# MCU.net
KiCad netlist of a schematic drawn in Altium Designer
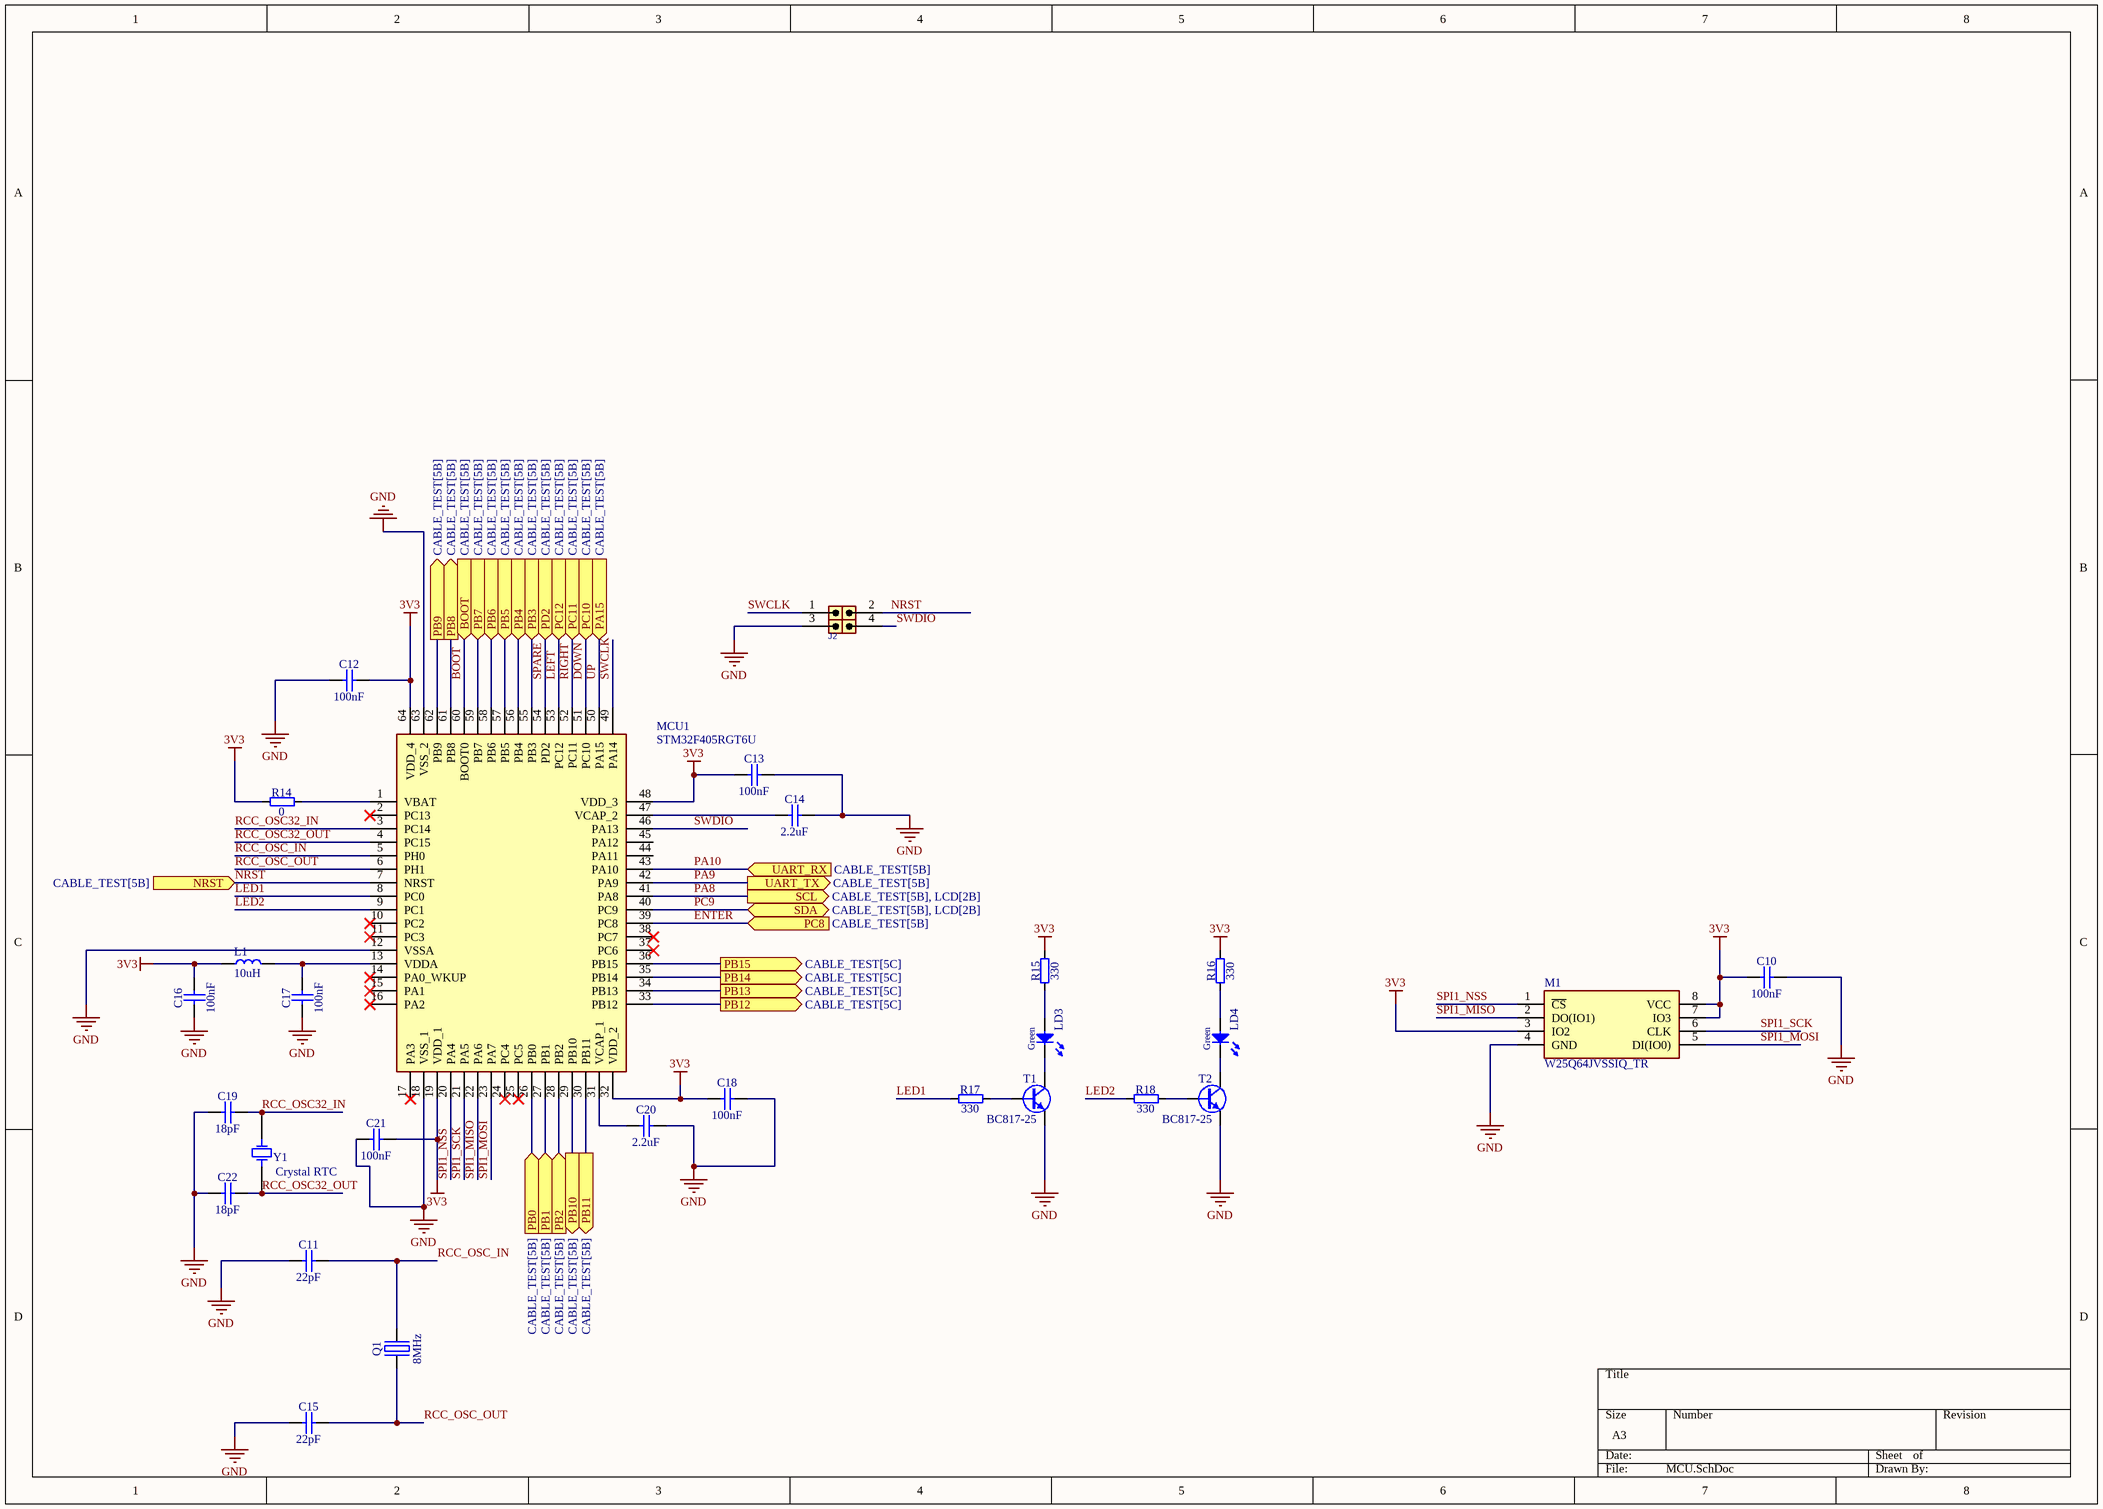
[diagram p0: MCU.SchDoc]

(export (version "E")
  (design (tool "Eeschema 10.0.6"))
  (components
    (comp (ref "C10")
      (value "100nF")
      (footprint "CAPC2012X135N")
      (description "Non-polarised capacitor")
      (fields
        (field (name "PART NUMBER") "CC0805_1.2PF_50V_0.25PF_NP0")
        (field (name "VOLTAGE") "50V")
        (field (name "AUTHOR") "CERN DEM JLC")
      )
      (libsource (lib "Capacitors") (part "Capacitor - non polarized"))
    )
    (comp (ref "C11")
      (value "22pF")
      (footprint "CAPC2012X135N")
      (description "Non-polarised capacitor")
      (fields
        (field (name "PART NUMBER") "CC0805_100NF_50V_10%_X7R")
        (field (name "VOLTAGE") "50V")
        (field (name "AUTHOR") "CERN DEM JLC")
      )
      (libsource (lib "Capacitors") (part "Capacitor - non polarized"))
    )
    (comp (ref "C12")
      (value "100nF")
      (footprint "CAPC2012X135N")
      (description "Non-polarised capacitor")
      (fields
        (field (name "PART NUMBER") "CC0805_100NF_50V_10%_X7R")
        (field (name "VOLTAGE") "50V")
        (field (name "AUTHOR") "CERN DEM JLC")
      )
      (libsource (lib "Capacitors") (part "Capacitor - non polarized"))
    )
    (comp (ref "C13")
      (value "100nF")
      (footprint "CAPC2012X135N")
      (description "Non-polarised capacitor")
      (fields
        (field (name "PART NUMBER") "CC0805_100NF_50V_10%_X7R")
        (field (name "VOLTAGE") "50V")
        (field (name "AUTHOR") "CERN DEM JLC")
      )
      (libsource (lib "Capacitors") (part "Capacitor - non polarized"))
    )
    (comp (ref "C14")
      (value "2.2uF")
      (footprint "CAPC2012X135N")
      (description "Non-polarised capacitor")
      (fields
        (field (name "PART NUMBER") "CC0805_100NF_50V_10%_X7R")
        (field (name "VOLTAGE") "50V")
        (field (name "AUTHOR") "CERN DEM JLC")
      )
      (libsource (lib "Capacitors") (part "Capacitor - non polarized"))
    )
    (comp (ref "C15")
      (value "22pF")
      (footprint "CAPC2012X135N")
      (description "Non-polarised capacitor")
      (fields
        (field (name "PART NUMBER") "CC0805_100NF_50V_10%_X7R")
        (field (name "VOLTAGE") "50V")
        (field (name "AUTHOR") "CERN DEM JLC")
      )
      (libsource (lib "Capacitors") (part "Capacitor - non polarized"))
    )
    (comp (ref "C16")
      (value "100nF")
      (footprint "CAPC2012X135N")
      (description "Non-polarised capacitor")
      (fields
        (field (name "PART NUMBER") "CC0805_100NF_50V_10%_X7R")
        (field (name "VOLTAGE") "50V")
        (field (name "AUTHOR") "CERN DEM JLC")
      )
      (libsource (lib "Capacitors") (part "Capacitor - non polarized"))
    )
    (comp (ref "C17")
      (value "100nF")
      (footprint "CAPC2012X135N")
      (description "Non-polarised capacitor")
      (fields
        (field (name "PART NUMBER") "CC0805_100NF_50V_10%_X7R")
        (field (name "VOLTAGE") "50V")
        (field (name "AUTHOR") "CERN DEM JLC")
      )
      (libsource (lib "Capacitors") (part "Capacitor - non polarized"))
    )
    (comp (ref "C18")
      (value "100nF")
      (footprint "CAPC2012X135N")
      (description "Non-polarised capacitor")
      (fields
        (field (name "PART NUMBER") "CC0805_100NF_50V_10%_X7R")
        (field (name "VOLTAGE") "50V")
        (field (name "AUTHOR") "CERN DEM JLC")
      )
      (libsource (lib "Capacitors") (part "Capacitor - non polarized"))
    )
    (comp (ref "C19")
      (value "18pF")
      (footprint "CAPC2012X135N")
      (description "Non-polarised capacitor")
      (fields
        (field (name "PART NUMBER") "CC0805_100NF_50V_10%_X7R")
        (field (name "VOLTAGE") "50V")
        (field (name "AUTHOR") "CERN DEM JLC")
      )
      (libsource (lib "Capacitors") (part "Capacitor - non polarized"))
    )
    (comp (ref "C20")
      (value "2.2uF")
      (footprint "CAPC2012X135N")
      (description "Non-polarised capacitor")
      (fields
        (field (name "PART NUMBER") "CC0805_100NF_50V_10%_X7R")
        (field (name "VOLTAGE") "50V")
        (field (name "AUTHOR") "CERN DEM JLC")
      )
      (libsource (lib "Capacitors") (part "Capacitor - non polarized"))
    )
    (comp (ref "C21")
      (value "100nF")
      (footprint "CAPC2012X135N")
      (description "Non-polarised capacitor")
      (fields
        (field (name "PART NUMBER") "CC0805_100NF_50V_10%_X7R")
        (field (name "VOLTAGE") "50V")
        (field (name "AUTHOR") "CERN DEM JLC")
      )
      (libsource (lib "Capacitors") (part "Capacitor - non polarized"))
    )
    (comp (ref "C22")
      (value "18pF")
      (footprint "CAPC2012X135N")
      (description "Non-polarised capacitor")
      (fields
        (field (name "PART NUMBER") "CC0805_100NF_50V_10%_X7R")
        (field (name "VOLTAGE") "50V")
        (field (name "AUTHOR") "CERN DEM JLC")
      )
      (libsource (lib "Capacitors") (part "Capacitor - non polarized"))
    )
    (comp (ref "J2")
      (value "Female Header dual 2")
      (footprint "HDR_F_2X2")
      (description "Female, pitch: 2.54mm")
      (libsource (lib "DSC-T.RControlBoard") (part "Female Header dual 2"))
    )
    (comp (ref "L1")
      (value "10uH")
      (footprint "L0805")
      (description "Inductor SMD NC 0805")
      (libsource (lib "DSC-T.RControlBoard") (part "Inductor SMD NC 0805"))
    )
    (comp (ref "LD3")
      (value "Green")
      (footprint "LED_3MM_GREEN_1C-2A")
      (description "LED Green 1C 2A")
      (fields
        (field (name "PART NUMBER") "LED_AVAGO_HLMP-1790")
        (field (name "MANUFACTURER") "AVAGO TECHNOLOGIES")
        (field (name "AUTHOR") "CERN DEM JLC")
      )
      (libsource (lib "ICs And Semiconductors") (part "LED Green 1C 2A"))
    )
    (comp (ref "LD4")
      (value "Green")
      (footprint "LED_3MM_GREEN_1C-2A")
      (description "LED Green 1C 2A")
      (fields
        (field (name "PART NUMBER") "LED_AVAGO_HLMP-1790")
        (field (name "MANUFACTURER") "AVAGO TECHNOLOGIES")
        (field (name "AUTHOR") "CERN DEM JLC")
      )
      (libsource (lib "ICs And Semiconductors") (part "LED Green 1C 2A"))
    )
    (comp (ref "M1")
      (value "W25Q64JVSSIQ_TR")
      (footprint "LORA:SOIC127P790X216-8N")
      (description "Integrated Circuit")
      (fields
        (field (name "MANUFACTURER_PART_NUMBER") "W25Q64JVSSIQ TR")
        (field (name "MOUSER PART NUMBER") "454-W25Q64JVSSIQTR")
      )
      (libsource (lib "*") (part "W25Q64JVSSIQ_TR"))
    )
    (comp (ref "MCU1")
      (value "STM32F405RGT6U")
      (footprint "LORA:QFP50P1200X1200X160-64N")
      (description "Integrated Circuit")
      (fields (field (name "MOUSER PART NUMBER") "511-STM32F405RGT6U"))
      (libsource (lib "*") (part "STM32F405RGT6U"))
    )
    (comp (ref "Q1")
      (value "8MHz")
      (footprint "XTAL_CTS_ATS")
      (description "Quartz Crystal")
      (fields
        (field (name "PART NUMBER") "XTAL_10MHZ_CTS_ATS100B-E")
        (field (name "MANUFACTURER") "CTS")
        (field (name "AUTHOR") "CERN DEM HF")
      )
      (libsource (lib "ICs And Semiconductors") (part "Quartz Crystal"))
    )
    (comp (ref "R14")
      (value "0")
      (footprint "RESC2012X60N")
      (description "Resistor - 1%")
      (fields
        (field (name "PART NUMBER") "R0805_24K_1%_0.125W_100PPM")
        (field (name "POWER") "0.125W")
        (field (name "AUTHOR") "CERN DEM JLC")
      )
      (libsource (lib "Resistors") (part "Resistor - 1%"))
    )
    (comp (ref "R15")
      (value "330")
      (footprint "RESC2012X60N")
      (description "Resistor - 1%")
      (fields
        (field (name "PART NUMBER") "R0805_24K_1%_0.125W_100PPM")
        (field (name "POWER") "0.125W")
        (field (name "AUTHOR") "CERN DEM JLC")
      )
      (libsource (lib "Resistors") (part "Resistor - 1%"))
    )
    (comp (ref "R16")
      (value "330")
      (footprint "RESC2012X60N")
      (description "Resistor - 1%")
      (fields
        (field (name "PART NUMBER") "R0805_24K_1%_0.125W_100PPM")
        (field (name "POWER") "0.125W")
        (field (name "AUTHOR") "CERN DEM JLC")
      )
      (libsource (lib "Resistors") (part "Resistor - 1%"))
    )
    (comp (ref "R17")
      (value "330")
      (footprint "RESC2012X60N")
      (description "Resistor - 1%")
      (fields
        (field (name "PART NUMBER") "R0805_24K_1%_0.125W_100PPM")
        (field (name "POWER") "0.125W")
        (field (name "AUTHOR") "CERN DEM JLC")
      )
      (libsource (lib "Resistors") (part "Resistor - 1%"))
    )
    (comp (ref "R18")
      (value "330")
      (footprint "RESC2012X60N")
      (description "Resistor - 1%")
      (fields
        (field (name "PART NUMBER") "R0805_24K_1%_0.125W_100PPM")
        (field (name "POWER") "0.125W")
        (field (name "AUTHOR") "CERN DEM JLC")
      )
      (libsource (lib "Resistors") (part "Resistor - 1%"))
    )
    (comp (ref "T1")
      (value "BC817-25")
      (footprint "SOT95P230X110-3N")
      (description "NPN Transistor")
      (fields (field (name "MANUFACTURER") "NXP SEMICONDUCTORS") (field (name "AUTHOR") "CERN DEM JLC"))
      (libsource (lib "ICs And Semiconductors") (part "NPN B1 E2 C3"))
    )
    (comp (ref "T2")
      (value "BC817-25")
      (footprint "SOT95P230X110-3N")
      (description "NPN Transistor")
      (fields (field (name "MANUFACTURER") "NXP SEMICONDUCTORS") (field (name "AUTHOR") "CERN DEM JLC"))
      (libsource (lib "ICs And Semiconductors") (part "NPN B1 E2 C3"))
    )
    (comp (ref "Y1")
      (value "Crystal RTC")
      (footprint "Crystal Clock")
      (description "Crystal")
      (libsource (lib "DSC-T.RControlBoard") (part "Crystal RTC"))
    )
  )
  (nets
    (net (code "1") (name "/BOOT") (class "Default")
      (node (ref "MCU1") (pin "60") (pinfunction "BOOT0_60") (pintype "passive"))
    )
    (net (code "2") (name "/DOWN") (class "Default")
      (node (ref "MCU1") (pin "51") (pinfunction "PC10_51") (pintype "passive"))
    )
    (net (code "3") (name "/ENTER") (class "Default")
      (node (ref "MCU1") (pin "39") (pinfunction "PC8_39") (pintype "passive"))
    )
    (net (code "4") (name "/LED1") (class "Default")
      (node (ref "MCU1") (pin "8") (pinfunction "PC0_8") (pintype "passive"))
      (node (ref "R17") (pin "1") (pinfunction "1_1") (pintype "passive"))
    )
    (net (code "5") (name "/LED2") (class "Default")
      (node (ref "MCU1") (pin "9") (pinfunction "PC1_9") (pintype "passive"))
      (node (ref "R18") (pin "1") (pinfunction "1_1") (pintype "passive"))
    )
    (net (code "6") (name "/LEFT") (class "Default")
      (node (ref "MCU1") (pin "53") (pinfunction "PC12_53") (pintype "passive"))
    )
    (net (code "7") (name "/NRST") (class "Default")
      (node (ref "J2") (pin "2") (pinfunction "2_2") (pintype "passive"))
      (node (ref "MCU1") (pin "7") (pinfunction "NRST_7") (pintype "passive"))
    )
    (net (code "8") (name "/PA8") (class "Default")
      (node (ref "MCU1") (pin "41") (pinfunction "PA8_41") (pintype "passive"))
    )
    (net (code "9") (name "/PA9") (class "Default")
      (node (ref "MCU1") (pin "42") (pinfunction "PA9_42") (pintype "passive"))
    )
    (net (code "10") (name "/PA10") (class "Default")
      (node (ref "MCU1") (pin "43") (pinfunction "PA10_43") (pintype "passive"))
    )
    (net (code "11") (name "/PB0") (class "Default")
      (node (ref "MCU1") (pin "26") (pinfunction "PB0_26") (pintype "passive"))
    )
    (net (code "12") (name "/PB1") (class "Default")
      (node (ref "MCU1") (pin "27") (pinfunction "PB1_27") (pintype "passive"))
    )
    (net (code "13") (name "/PB2") (class "Default")
      (node (ref "MCU1") (pin "28") (pinfunction "PB2_28") (pintype "passive"))
    )
    (net (code "14") (name "/PB3") (class "Default")
      (node (ref "MCU1") (pin "55") (pinfunction "PB3_55") (pintype "passive"))
    )
    (net (code "15") (name "/PB4") (class "Default")
      (node (ref "MCU1") (pin "56") (pinfunction "PB4_56") (pintype "passive"))
    )
    (net (code "16") (name "/PB5") (class "Default")
      (node (ref "MCU1") (pin "57") (pinfunction "PB5_57") (pintype "passive"))
    )
    (net (code "17") (name "/PB6") (class "Default")
      (node (ref "MCU1") (pin "58") (pinfunction "PB6_58") (pintype "passive"))
    )
    (net (code "18") (name "/PB7") (class "Default")
      (node (ref "MCU1") (pin "59") (pinfunction "PB7_59") (pintype "passive"))
    )
    (net (code "19") (name "/PB8") (class "Default")
      (node (ref "MCU1") (pin "61") (pinfunction "PB8_61") (pintype "passive"))
    )
    (net (code "20") (name "/PB9") (class "Default")
      (node (ref "MCU1") (pin "62") (pinfunction "PB9_62") (pintype "passive"))
    )
    (net (code "21") (name "/PB10") (class "Default")
      (node (ref "MCU1") (pin "29") (pinfunction "PB10_29") (pintype "passive"))
    )
    (net (code "22") (name "/PB11") (class "Default")
      (node (ref "MCU1") (pin "30") (pinfunction "PB11_30") (pintype "passive"))
    )
    (net (code "23") (name "/PB12") (class "Default")
      (node (ref "MCU1") (pin "33") (pinfunction "PB12_33") (pintype "passive"))
    )
    (net (code "24") (name "/PB13") (class "Default")
      (node (ref "MCU1") (pin "34") (pinfunction "PB13_34") (pintype "passive"))
    )
    (net (code "25") (name "/PB14") (class "Default")
      (node (ref "MCU1") (pin "35") (pinfunction "PB14_35") (pintype "passive"))
    )
    (net (code "26") (name "/PB15") (class "Default")
      (node (ref "MCU1") (pin "36") (pinfunction "PB15_36") (pintype "passive"))
    )
    (net (code "27") (name "/PC9") (class "Default")
      (node (ref "MCU1") (pin "40") (pinfunction "PC9_40") (pintype "passive"))
    )
    (net (code "28") (name "/RCC_OSC32_IN") (class "Default")
      (node (ref "C19") (pin "2") (pinfunction "2_2") (pintype "passive"))
      (node (ref "MCU1") (pin "3") (pinfunction "PC14_3") (pintype "passive"))
      (node (ref "Y1") (pin "1") (pinfunction "1_1") (pintype "passive"))
    )
    (net (code "29") (name "/RCC_OSC32_OUT") (class "Default")
      (node (ref "C22") (pin "2") (pinfunction "2_2") (pintype "passive"))
      (node (ref "MCU1") (pin "4") (pinfunction "PC15_4") (pintype "passive"))
      (node (ref "Y1") (pin "2") (pinfunction "2_2") (pintype "passive"))
    )
    (net (code "30") (name "/RCC_OSC_IN") (class "Default")
      (node (ref "C11") (pin "2") (pinfunction "2_2") (pintype "passive"))
      (node (ref "MCU1") (pin "5") (pinfunction "PH0_5") (pintype "passive"))
      (node (ref "Q1") (pin "2") (pinfunction "OSC2_2") (pintype "passive"))
    )
    (net (code "31") (name "/RCC_OSC_OUT") (class "Default")
      (node (ref "C15") (pin "2") (pinfunction "2_2") (pintype "passive"))
      (node (ref "MCU1") (pin "6") (pinfunction "PH1_6") (pintype "passive"))
      (node (ref "Q1") (pin "1") (pinfunction "OSC1_1") (pintype "passive"))
    )
    (net (code "32") (name "/RIGHT") (class "Default")
      (node (ref "MCU1") (pin "52") (pinfunction "PC11_52") (pintype "passive"))
    )
    (net (code "33") (name "/SPARE") (class "Default")
      (node (ref "MCU1") (pin "54") (pinfunction "PD2_54") (pintype "passive"))
    )
    (net (code "34") (name "/SPI1_MISO") (class "Default")
      (node (ref "M1") (pin "2") (pinfunction "DO(IO1)_2") (pintype "passive"))
      (node (ref "MCU1") (pin "22") (pinfunction "PA6_22") (pintype "passive"))
    )
    (net (code "35") (name "/SPI1_MOSI") (class "Default")
      (node (ref "M1") (pin "5") (pinfunction "DI(IO0)_5") (pintype "passive"))
      (node (ref "MCU1") (pin "23") (pinfunction "PA7_23") (pintype "passive"))
    )
    (net (code "36") (name "/SPI1_NSS") (class "Default")
      (node (ref "M1") (pin "1") (pinfunction "~{CS}_1") (pintype "passive"))
      (node (ref "MCU1") (pin "20") (pinfunction "PA4_20") (pintype "passive"))
    )
    (net (code "37") (name "/SPI1_SCK") (class "Default")
      (node (ref "M1") (pin "6") (pinfunction "CLK_6") (pintype "passive"))
      (node (ref "MCU1") (pin "21") (pinfunction "PA5_21") (pintype "passive"))
    )
    (net (code "38") (name "/SWCLK") (class "Default")
      (node (ref "J2") (pin "1") (pinfunction "1_1") (pintype "passive"))
      (node (ref "MCU1") (pin "49") (pinfunction "PA14_49") (pintype "passive"))
    )
    (net (code "39") (name "/SWDIO") (class "Default")
      (node (ref "J2") (pin "4") (pinfunction "4_4") (pintype "passive"))
      (node (ref "MCU1") (pin "46") (pinfunction "PA13_46") (pintype "passive"))
    )
    (net (code "40") (name "/UP") (class "Default")
      (node (ref "MCU1") (pin "50") (pinfunction "PA15_50") (pintype "passive"))
    )
    (net (code "41") (name "3V3") (class "Default")
      (node (ref "C10") (pin "1") (pinfunction "1_1") (pintype "passive"))
      (node (ref "C12") (pin "2") (pinfunction "2_2") (pintype "passive"))
      (node (ref "C13") (pin "1") (pinfunction "1_1") (pintype "passive"))
      (node (ref "C16") (pin "2") (pinfunction "2_2") (pintype "passive"))
      (node (ref "C18") (pin "1") (pinfunction "1_1") (pintype "passive"))
      (node (ref "C21") (pin "2") (pinfunction "2_2") (pintype "passive"))
      (node (ref "L1") (pin "1") (pinfunction "1_1") (pintype "passive"))
      (node (ref "M1") (pin "3") (pinfunction "IO2_3") (pintype "passive"))
      (node (ref "M1") (pin "7") (pinfunction "IO3_7") (pintype "passive"))
      (node (ref "M1") (pin "8") (pinfunction "VCC_8") (pintype "passive"))
      (node (ref "MCU1") (pin "19") (pinfunction "VDD_1_19") (pintype "passive"))
      (node (ref "MCU1") (pin "32") (pinfunction "VDD_2_32") (pintype "passive"))
      (node (ref "MCU1") (pin "48") (pinfunction "VDD_3_48") (pintype "passive"))
      (node (ref "MCU1") (pin "64") (pinfunction "VDD_4_64") (pintype "passive"))
      (node (ref "R14") (pin "1") (pinfunction "1_1") (pintype "passive"))
      (node (ref "R15") (pin "2") (pinfunction "2_2") (pintype "passive"))
      (node (ref "R16") (pin "2") (pinfunction "2_2") (pintype "passive"))
    )
    (net (code "42") (name "GND") (class "Default")
      (node (ref "C10") (pin "2") (pinfunction "2_2") (pintype "passive"))
      (node (ref "C11") (pin "1") (pinfunction "1_1") (pintype "passive"))
      (node (ref "C12") (pin "1") (pinfunction "1_1") (pintype "passive"))
      (node (ref "C13") (pin "2") (pinfunction "2_2") (pintype "passive"))
      (node (ref "C14") (pin "2") (pinfunction "2_2") (pintype "passive"))
      (node (ref "C15") (pin "1") (pinfunction "1_1") (pintype "passive"))
      (node (ref "C16") (pin "1") (pinfunction "1_1") (pintype "passive"))
      (node (ref "C17") (pin "1") (pinfunction "1_1") (pintype "passive"))
      (node (ref "C18") (pin "2") (pinfunction "2_2") (pintype "passive"))
      (node (ref "C19") (pin "1") (pinfunction "1_1") (pintype "passive"))
      (node (ref "C20") (pin "2") (pinfunction "2_2") (pintype "passive"))
      (node (ref "C21") (pin "1") (pinfunction "1_1") (pintype "passive"))
      (node (ref "C22") (pin "1") (pinfunction "1_1") (pintype "passive"))
      (node (ref "J2") (pin "3") (pinfunction "3_3") (pintype "passive"))
      (node (ref "M1") (pin "4") (pinfunction "GND_4") (pintype "passive"))
      (node (ref "MCU1") (pin "12") (pinfunction "VSSA_12") (pintype "passive"))
      (node (ref "MCU1") (pin "18") (pinfunction "VSS_1_18") (pintype "passive"))
      (node (ref "MCU1") (pin "63") (pinfunction "VSS_2_63") (pintype "passive"))
      (node (ref "T1") (pin "2") (pinfunction "E_2") (pintype "passive"))
      (node (ref "T2") (pin "2") (pinfunction "E_2") (pintype "passive"))
    )
    (net (code "43") (name "Net-(LD3-A)") (class "Default")
      (node (ref "LD3") (pin "2") (pinfunction "A_2") (pintype "passive"))
      (node (ref "R15") (pin "1") (pinfunction "1_1") (pintype "passive"))
    )
    (net (code "44") (name "Net-(LD3-C)") (class "Default")
      (node (ref "LD3") (pin "1") (pinfunction "C_1") (pintype "passive"))
      (node (ref "T1") (pin "3") (pinfunction "C_3") (pintype "passive"))
    )
    (net (code "45") (name "Net-(LD4-A)") (class "Default")
      (node (ref "LD4") (pin "2") (pinfunction "A_2") (pintype "passive"))
      (node (ref "R16") (pin "1") (pinfunction "1_1") (pintype "passive"))
    )
    (net (code "46") (name "Net-(LD4-C)") (class "Default")
      (node (ref "LD4") (pin "1") (pinfunction "C_1") (pintype "passive"))
      (node (ref "T2") (pin "3") (pinfunction "C_3") (pintype "passive"))
    )
    (net (code "47") (name "Net-(MCU1-VBAT)") (class "Default")
      (node (ref "MCU1") (pin "1") (pinfunction "VBAT_1") (pintype "passive"))
      (node (ref "R14") (pin "2") (pinfunction "2_2") (pintype "passive"))
    )
    (net (code "48") (name "Net-(MCU1-VCAP_1)") (class "Default")
      (node (ref "C20") (pin "1") (pinfunction "1_1") (pintype "passive"))
      (node (ref "MCU1") (pin "31") (pinfunction "VCAP_1_31") (pintype "passive"))
    )
    (net (code "49") (name "Net-(MCU1-VCAP_2)") (class "Default")
      (node (ref "C14") (pin "1") (pinfunction "1_1") (pintype "passive"))
      (node (ref "MCU1") (pin "47") (pinfunction "VCAP_2_47") (pintype "passive"))
    )
    (net (code "50") (name "Net-(MCU1-VDDA)") (class "Default")
      (node (ref "C17") (pin "2") (pinfunction "2_2") (pintype "passive"))
      (node (ref "L1") (pin "2") (pinfunction "2_2") (pintype "passive"))
      (node (ref "MCU1") (pin "13") (pinfunction "VDDA_13") (pintype "passive"))
    )
    (net (code "51") (name "Net-(T1-B)") (class "Default")
      (node (ref "R17") (pin "2") (pinfunction "2_2") (pintype "passive"))
      (node (ref "T1") (pin "1") (pinfunction "B_1") (pintype "passive"))
    )
    (net (code "52") (name "Net-(T2-B)") (class "Default")
      (node (ref "R18") (pin "2") (pinfunction "2_2") (pintype "passive"))
      (node (ref "T2") (pin "1") (pinfunction "B_1") (pintype "passive"))
    )
    (net (code "53") (name "unconnected-(MCU1-PA0_WKUP-Pad14)") (class "Default")
      (node (ref "MCU1") (pin "14") (pinfunction "PA0_WKUP_14") (pintype "passive+no_connect"))
    )
    (net (code "54") (name "unconnected-(MCU1-PA1-Pad15)") (class "Default")
      (node (ref "MCU1") (pin "15") (pinfunction "PA1_15") (pintype "passive+no_connect"))
    )
    (net (code "55") (name "unconnected-(MCU1-PA2-Pad16)") (class "Default")
      (node (ref "MCU1") (pin "16") (pinfunction "PA2_16") (pintype "passive+no_connect"))
    )
    (net (code "56") (name "unconnected-(MCU1-PA3-Pad17)") (class "Default")
      (node (ref "MCU1") (pin "17") (pinfunction "PA3_17") (pintype "passive+no_connect"))
    )
    (net (code "57") (name "unconnected-(MCU1-PA11-Pad44)") (class "Default")
      (node (ref "MCU1") (pin "44") (pinfunction "PA11_44") (pintype "passive"))
    )
    (net (code "58") (name "unconnected-(MCU1-PA12-Pad45)") (class "Default")
      (node (ref "MCU1") (pin "45") (pinfunction "PA12_45") (pintype "passive"))
    )
    (net (code "59") (name "unconnected-(MCU1-PC2-Pad10)") (class "Default")
      (node (ref "MCU1") (pin "10") (pinfunction "PC2_10") (pintype "passive+no_connect"))
    )
    (net (code "60") (name "unconnected-(MCU1-PC3-Pad11)") (class "Default")
      (node (ref "MCU1") (pin "11") (pinfunction "PC3_11") (pintype "passive+no_connect"))
    )
    (net (code "61") (name "unconnected-(MCU1-PC4-Pad24)") (class "Default")
      (node (ref "MCU1") (pin "24") (pinfunction "PC4_24") (pintype "passive+no_connect"))
    )
    (net (code "62") (name "unconnected-(MCU1-PC5-Pad25)") (class "Default")
      (node (ref "MCU1") (pin "25") (pinfunction "PC5_25") (pintype "passive+no_connect"))
    )
    (net (code "63") (name "unconnected-(MCU1-PC6-Pad37)") (class "Default")
      (node (ref "MCU1") (pin "37") (pinfunction "PC6_37") (pintype "passive+no_connect"))
    )
    (net (code "64") (name "unconnected-(MCU1-PC7-Pad38)") (class "Default")
      (node (ref "MCU1") (pin "38") (pinfunction "PC7_38") (pintype "passive+no_connect"))
    )
    (net (code "65") (name "unconnected-(MCU1-PC13-Pad2)") (class "Default")
      (node (ref "MCU1") (pin "2") (pinfunction "PC13_2") (pintype "passive+no_connect"))
    )
  )
)
